# BV100011_ControlDO.net
KiCad netlist of a schematic drawn in Altium Designer
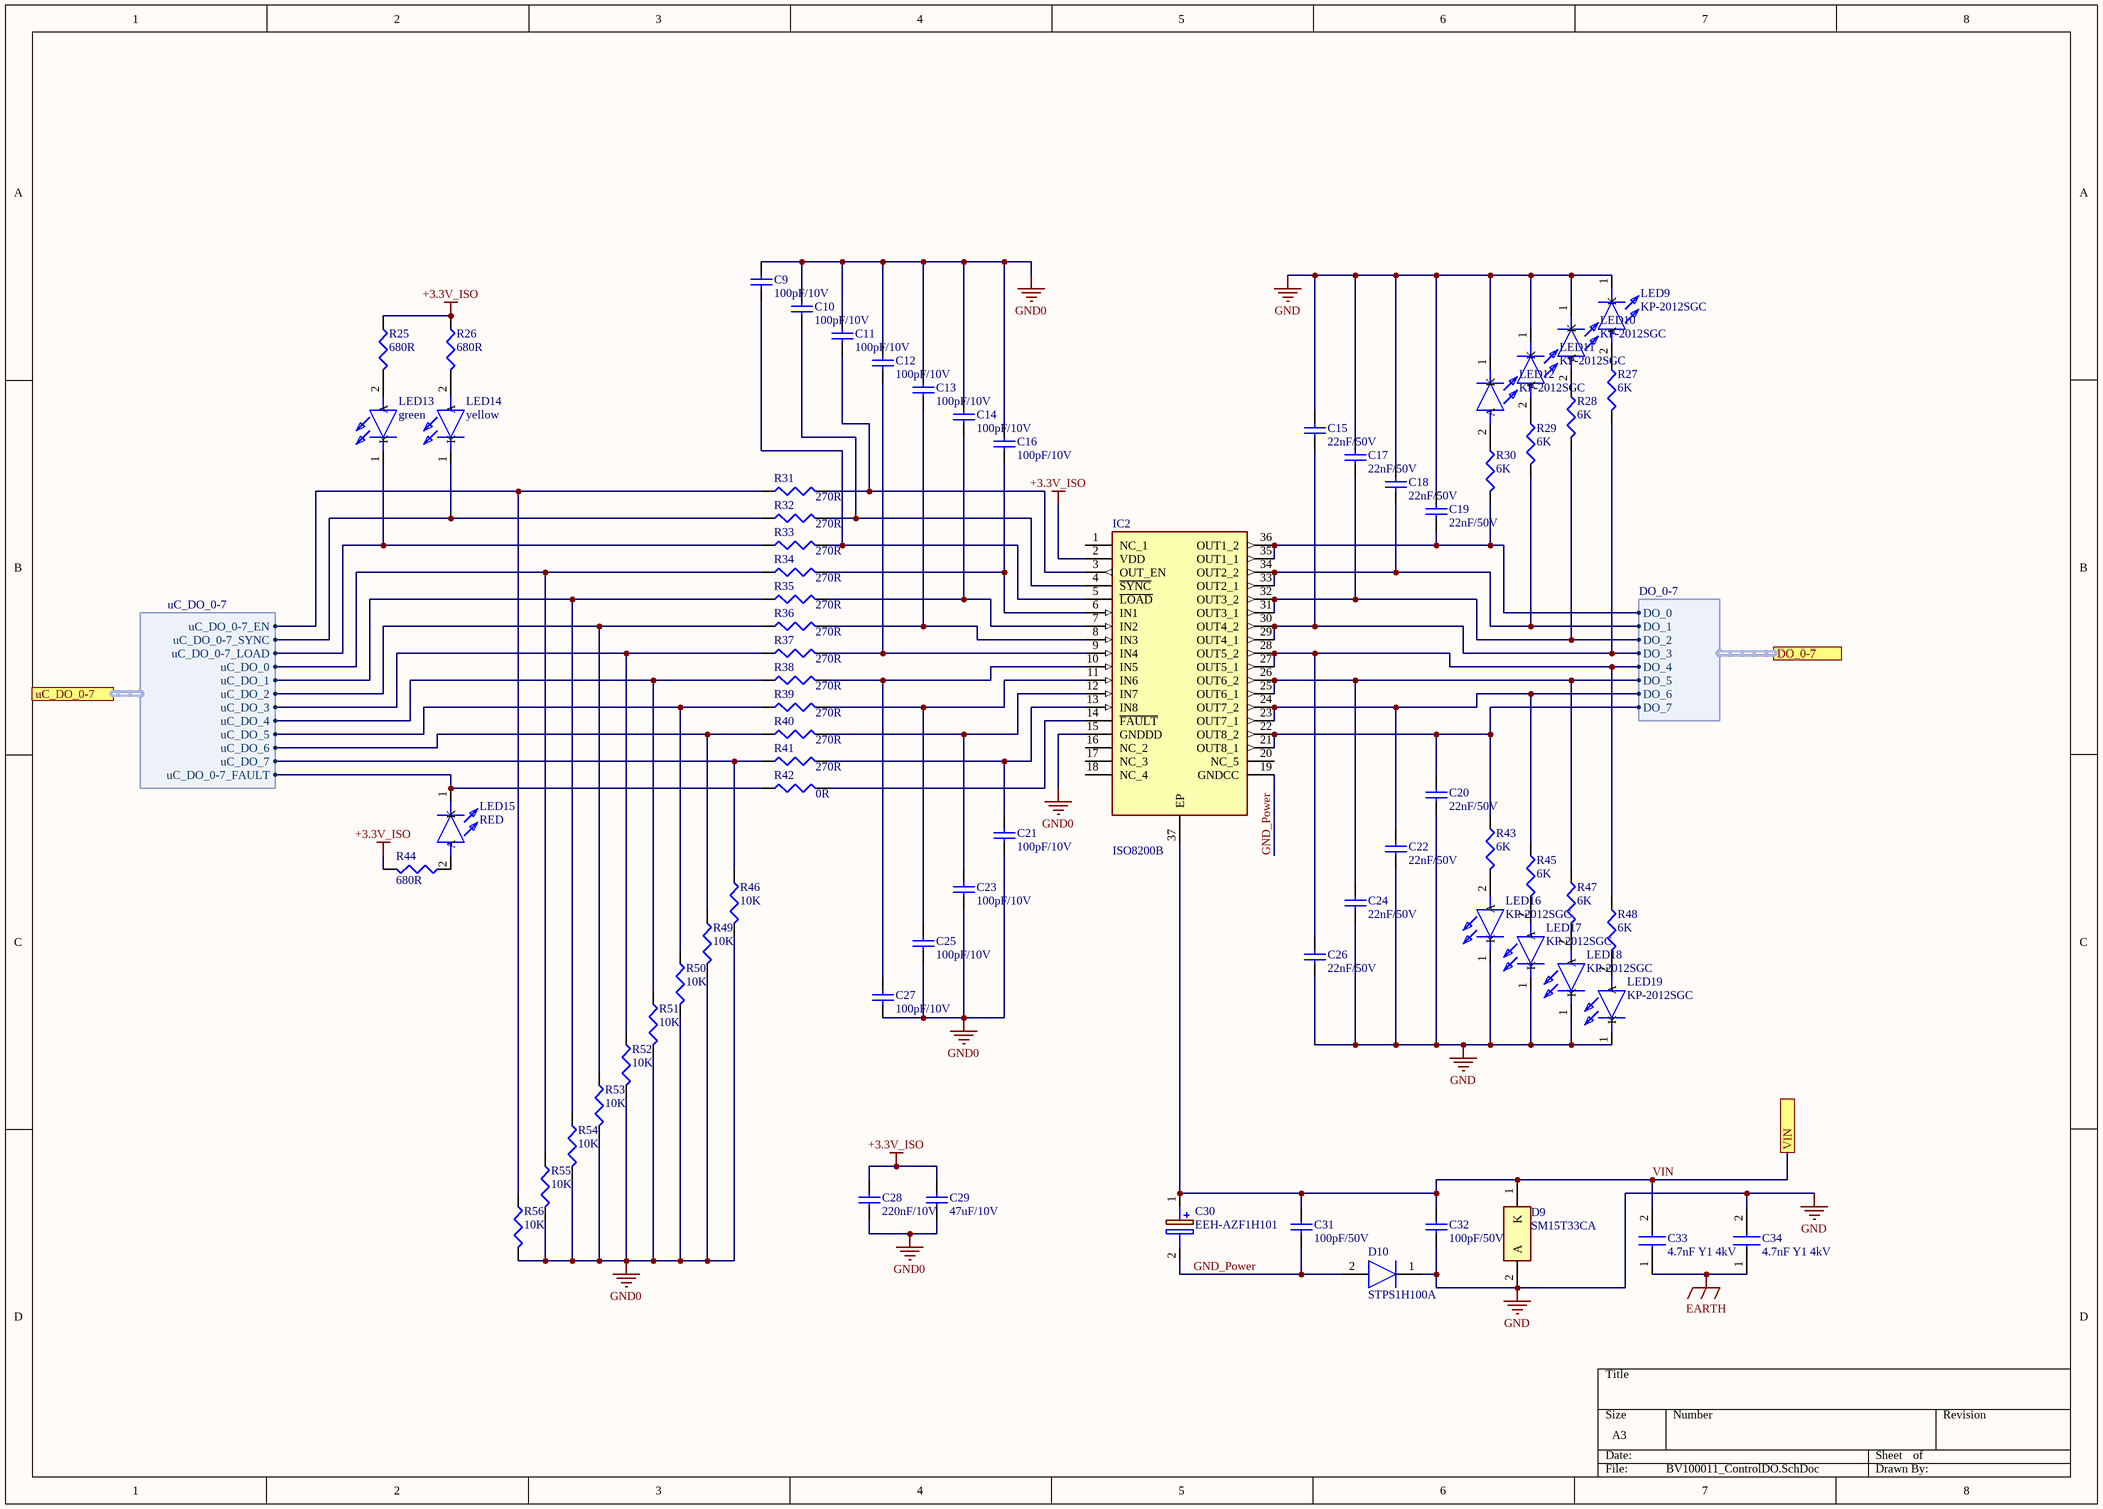
[diagram p0: BV100011_ControlDO.SchDoc]

(export (version "E")
  (design (tool "Eeschema 10.0.6"))
  (components
    (comp (ref "C9")
      (value "100pF/10V")
      (footprint "0402")
      (description "Capacitor (Semiconductor SIM Model)")
      (fields (field (name "PUBLISHER") "Altium Limited"))
      (libsource (lib "Miscellaneous Devices") (part "Cap Semi"))
    )
    (comp (ref "C10")
      (value "100pF/10V")
      (footprint "0402")
      (description "Capacitor (Semiconductor SIM Model)")
      (fields (field (name "PUBLISHER") "Altium Limited"))
      (libsource (lib "Miscellaneous Devices") (part "Cap Semi"))
    )
    (comp (ref "C11")
      (value "100pF/10V")
      (footprint "0402")
      (description "Capacitor (Semiconductor SIM Model)")
      (fields (field (name "PUBLISHER") "Altium Limited"))
      (libsource (lib "Miscellaneous Devices") (part "Cap Semi"))
    )
    (comp (ref "C12")
      (value "100pF/10V")
      (footprint "0402")
      (description "Capacitor (Semiconductor SIM Model)")
      (fields (field (name "PUBLISHER") "Altium Limited"))
      (libsource (lib "Miscellaneous Devices") (part "Cap Semi"))
    )
    (comp (ref "C13")
      (value "100pF/10V")
      (footprint "0402")
      (description "Capacitor (Semiconductor SIM Model)")
      (fields (field (name "PUBLISHER") "Altium Limited"))
      (libsource (lib "Miscellaneous Devices") (part "Cap Semi"))
    )
    (comp (ref "C14")
      (value "100pF/10V")
      (footprint "0402")
      (description "Capacitor (Semiconductor SIM Model)")
      (fields (field (name "PUBLISHER") "Altium Limited"))
      (libsource (lib "Miscellaneous Devices") (part "Cap Semi"))
    )
    (comp (ref "C15")
      (value "22nF/50V")
      (footprint "C1210")
      (description "Capacitor (Semiconductor SIM Model)")
      (fields (field (name "PUBLISHER") "Altium Limited"))
      (libsource (lib "Miscellaneous Devices") (part "Cap Semi"))
    )
    (comp (ref "C16")
      (value "100pF/10V")
      (footprint "0402")
      (description "Capacitor (Semiconductor SIM Model)")
      (fields (field (name "PUBLISHER") "Altium Limited"))
      (libsource (lib "Miscellaneous Devices") (part "Cap Semi"))
    )
    (comp (ref "C17")
      (value "22nF/50V")
      (footprint "C1210")
      (description "Capacitor (Semiconductor SIM Model)")
      (fields (field (name "PUBLISHER") "Altium Limited"))
      (libsource (lib "Miscellaneous Devices") (part "Cap Semi"))
    )
    (comp (ref "C18")
      (value "22nF/50V")
      (footprint "C1210")
      (description "Capacitor (Semiconductor SIM Model)")
      (fields (field (name "PUBLISHER") "Altium Limited"))
      (libsource (lib "Miscellaneous Devices") (part "Cap Semi"))
    )
    (comp (ref "C19")
      (value "22nF/50V")
      (footprint "C1210")
      (description "Capacitor (Semiconductor SIM Model)")
      (fields (field (name "PUBLISHER") "Altium Limited"))
      (libsource (lib "Miscellaneous Devices") (part "Cap Semi"))
    )
    (comp (ref "C20")
      (value "22nF/50V")
      (footprint "C1210")
      (description "Capacitor (Semiconductor SIM Model)")
      (fields (field (name "PUBLISHER") "Altium Limited"))
      (libsource (lib "Miscellaneous Devices") (part "Cap Semi"))
    )
    (comp (ref "C21")
      (value "100pF/10V")
      (footprint "0402")
      (description "Capacitor (Semiconductor SIM Model)")
      (fields (field (name "PUBLISHER") "Altium Limited"))
      (libsource (lib "Miscellaneous Devices") (part "Cap Semi"))
    )
    (comp (ref "C22")
      (value "22nF/50V")
      (footprint "C1210")
      (description "Capacitor (Semiconductor SIM Model)")
      (fields (field (name "PUBLISHER") "Altium Limited"))
      (libsource (lib "Miscellaneous Devices") (part "Cap Semi"))
    )
    (comp (ref "C23")
      (value "100pF/10V")
      (footprint "0402")
      (description "Capacitor (Semiconductor SIM Model)")
      (fields (field (name "PUBLISHER") "Altium Limited"))
      (libsource (lib "Miscellaneous Devices") (part "Cap Semi"))
    )
    (comp (ref "C24")
      (value "22nF/50V")
      (footprint "C1210")
      (description "Capacitor (Semiconductor SIM Model)")
      (fields (field (name "PUBLISHER") "Altium Limited"))
      (libsource (lib "Miscellaneous Devices") (part "Cap Semi"))
    )
    (comp (ref "C25")
      (value "100pF/10V")
      (footprint "0402")
      (description "Capacitor (Semiconductor SIM Model)")
      (fields (field (name "PUBLISHER") "Altium Limited"))
      (libsource (lib "Miscellaneous Devices") (part "Cap Semi"))
    )
    (comp (ref "C26")
      (value "22nF/50V")
      (footprint "C1210")
      (description "Capacitor (Semiconductor SIM Model)")
      (fields (field (name "PUBLISHER") "Altium Limited"))
      (libsource (lib "Miscellaneous Devices") (part "Cap Semi"))
    )
    (comp (ref "C27")
      (value "100pF/10V")
      (footprint "0402")
      (description "Capacitor (Semiconductor SIM Model)")
      (fields (field (name "PUBLISHER") "Altium Limited"))
      (libsource (lib "Miscellaneous Devices") (part "Cap Semi"))
    )
    (comp (ref "C28")
      (value "220nF/10V")
      (footprint "C1210")
      (description "Capacitor (Semiconductor SIM Model)")
      (fields (field (name "PUBLISHER") "Altium Limited"))
      (libsource (lib "Miscellaneous Devices") (part "Cap Semi"))
    )
    (comp (ref "C29")
      (value "47uF/10V")
      (footprint "C1210")
      (description "Capacitor (Semiconductor SIM Model)")
      (fields (field (name "PUBLISHER") "Altium Limited"))
      (libsource (lib "Miscellaneous Devices") (part "Cap Semi"))
    )
    (comp (ref "C30")
      (value "EEH-AZF1H101")
      (footprint "CAPPRD500W65D1000H1050")
      (description "Capacitor Polarised")
      (fields (field (name "MOUSER PART NUMBER") "667-EEH-AZF1H101"))
      (libsource (lib "Electrolytic Capacitors") (part "EEH-AZF1H101"))
    )
    (comp (ref "C31")
      (value "100pF/50V")
      (footprint "C1210")
      (description "Capacitor (Semiconductor SIM Model)")
      (fields (field (name "PUBLISHER") "Altium Limited"))
      (libsource (lib "Miscellaneous Devices") (part "Cap Semi"))
    )
    (comp (ref "C32")
      (value "100pF/50V")
      (footprint "C1210")
      (description "Capacitor (Semiconductor SIM Model)")
      (fields (field (name "PUBLISHER") "Altium Limited"))
      (libsource (lib "Miscellaneous Devices") (part "Cap Semi"))
    )
    (comp (ref "C33")
      (value "4.7nF Y1 4kV")
      (footprint "VY1472M63Y5UQ63V0")
      (description "Capacitor")
      (fields (field (name "MANUFACTURER_PART_NUMBER") "VY1472M63Y5UQ63V0"))
      (libsource (lib "VY1472M63Y5UQ6V0") (part "VY1472M63Y5UQ63V0"))
    )
    (comp (ref "C34")
      (value "4.7nF Y1 4kV")
      (footprint "VY1472M63Y5UQ63V0")
      (description "Capacitor")
      (fields (field (name "MANUFACTURER_PART_NUMBER") "VY1472M63Y5UQ63V0"))
      (libsource (lib "VY1472M63Y5UQ6V0") (part "VY1472M63Y5UQ63V0"))
    )
    (comp (ref "D9")
      (value "SM15T33CA")
      (footprint "DIONM8059X265N")
      (description "Diode")
      (fields (field (name "MOUSER PART NUMBER") "511-SM15T33CA") (field (name "RS PART NUMBER") "9196428"))
      (libsource (lib "SM15T33CA") (part "SM15T33CA"))
    )
    (comp (ref "D10")
      (value "STPS1H100A")
      (footprint "DIOM5126X265N")
      (description "Diode")
      (fields (field (name "MOUSER PART NUMBER") "511-STPS1H100A") (field (name "RS PART NUMBER") "0249892P"))
      (libsource (lib "STPS1H100A") (part "STPS1H100A"))
    )
    (comp (ref "IC2")
      (value "ISO8200B")
      (footprint "SOP65P1420X360-37N")
      (description "Integrated Circuit")
      (fields (field (name "MOUSER PART NUMBER") "511-ISO8200B"))
      (libsource (lib "ISO8200B") (part "ISO8200B"))
    )
    (comp (ref "LED9")
      (value "KP-2012SGC")
      (footprint "LEDC2012X110N")
      (description "LED")
      (fields (field (name "RS PART NUMBER") "4663807"))
      (libsource (lib "POWER_LED") (part "KP-2012SGC"))
    )
    (comp (ref "LED10")
      (value "KP-2012SGC")
      (footprint "LEDC2012X110N")
      (description "LED")
      (fields (field (name "RS PART NUMBER") "4663807"))
      (libsource (lib "POWER_LED") (part "KP-2012SGC"))
    )
    (comp (ref "LED11")
      (value "KP-2012SGC")
      (footprint "LEDC2012X110N")
      (description "LED")
      (fields (field (name "RS PART NUMBER") "4663807"))
      (libsource (lib "POWER_LED") (part "KP-2012SGC"))
    )
    (comp (ref "LED12")
      (value "KP-2012SGC")
      (footprint "LEDC2012X110N")
      (description "LED")
      (fields (field (name "RS PART NUMBER") "4663807"))
      (libsource (lib "POWER_LED") (part "KP-2012SGC"))
    )
    (comp (ref "LED13")
      (value "green")
      (footprint "LEDC2012X110N")
      (description "LED")
      (fields
        (field (name "MANUFACTURER_PART_NUMBER") "KP-2012SGC")
        (field (name "RS PART NUMBER") "4663807")
      )
      (libsource (lib "POWER_LED") (part "KP-2012SGC"))
    )
    (comp (ref "LED14")
      (value "yellow")
      (footprint "LEDC2012X110N")
      (description "LED")
      (fields
        (field (name "MANUFACTURER_PART_NUMBER") "KP-2012SGC")
        (field (name "RS PART NUMBER") "4663807")
      )
      (libsource (lib "POWER_LED") (part "KP-2012SGC"))
    )
    (comp (ref "LED15")
      (value "RED")
      (footprint "LEDC2012X110N")
      (description "LED")
      (fields
        (field (name "MANUFACTURER_PART_NUMBER") "KP-2012SGC")
        (field (name "RS PART NUMBER") "4663807")
      )
      (libsource (lib "POWER_LED") (part "KP-2012SGC"))
    )
    (comp (ref "LED16")
      (value "KP-2012SGC")
      (footprint "LEDC2012X110N")
      (description "LED")
      (fields (field (name "RS PART NUMBER") "4663807"))
      (libsource (lib "POWER_LED") (part "KP-2012SGC"))
    )
    (comp (ref "LED17")
      (value "KP-2012SGC")
      (footprint "LEDC2012X110N")
      (description "LED")
      (fields (field (name "RS PART NUMBER") "4663807"))
      (libsource (lib "POWER_LED") (part "KP-2012SGC"))
    )
    (comp (ref "LED18")
      (value "KP-2012SGC")
      (footprint "LEDC2012X110N")
      (description "LED")
      (fields (field (name "RS PART NUMBER") "4663807"))
      (libsource (lib "POWER_LED") (part "KP-2012SGC"))
    )
    (comp (ref "LED19")
      (value "KP-2012SGC")
      (footprint "LEDC2012X110N")
      (description "LED")
      (fields (field (name "RS PART NUMBER") "4663807"))
      (libsource (lib "POWER_LED") (part "KP-2012SGC"))
    )
    (comp (ref "R25")
      (value "680R")
      (footprint "0402")
      (description "Resistor")
      (fields (field (name "PUBLISHER") "Altium Limited"))
      (libsource (lib "Miscellaneous Devices") (part "Res3"))
    )
    (comp (ref "R26")
      (value "680R")
      (footprint "0402")
      (description "Resistor")
      (fields (field (name "PUBLISHER") "Altium Limited"))
      (libsource (lib "Miscellaneous Devices") (part "Res3"))
    )
    (comp (ref "R27")
      (value "6K")
      (footprint "0805R")
      (description "Resistor")
      (fields (field (name "PUBLISHER") "Altium Limited"))
      (libsource (lib "Miscellaneous Devices") (part "Res3"))
    )
    (comp (ref "R28")
      (value "6K")
      (footprint "0805R")
      (description "Resistor")
      (fields (field (name "PUBLISHER") "Altium Limited"))
      (libsource (lib "Miscellaneous Devices") (part "Res3"))
    )
    (comp (ref "R29")
      (value "6K")
      (footprint "0805R")
      (description "Resistor")
      (fields (field (name "PUBLISHER") "Altium Limited"))
      (libsource (lib "Miscellaneous Devices") (part "Res3"))
    )
    (comp (ref "R30")
      (value "6K")
      (footprint "0805R")
      (description "Resistor")
      (fields (field (name "PUBLISHER") "Altium Limited"))
      (libsource (lib "Miscellaneous Devices") (part "Res3"))
    )
    (comp (ref "R31")
      (value "270R")
      (footprint "0402")
      (description "Resistor")
      (fields (field (name "PUBLISHER") "Altium Limited"))
      (libsource (lib "Miscellaneous Devices") (part "Res3"))
    )
    (comp (ref "R32")
      (value "270R")
      (footprint "0402")
      (description "Resistor")
      (fields (field (name "PUBLISHER") "Altium Limited"))
      (libsource (lib "Miscellaneous Devices") (part "Res3"))
    )
    (comp (ref "R33")
      (value "270R")
      (footprint "0402")
      (description "Resistor")
      (fields (field (name "PUBLISHER") "Altium Limited"))
      (libsource (lib "Miscellaneous Devices") (part "Res3"))
    )
    (comp (ref "R34")
      (value "270R")
      (footprint "0402")
      (description "Resistor")
      (fields (field (name "PUBLISHER") "Altium Limited"))
      (libsource (lib "Miscellaneous Devices") (part "Res3"))
    )
    (comp (ref "R35")
      (value "270R")
      (footprint "0402")
      (description "Resistor")
      (fields (field (name "PUBLISHER") "Altium Limited"))
      (libsource (lib "Miscellaneous Devices") (part "Res3"))
    )
    (comp (ref "R36")
      (value "270R")
      (footprint "0402")
      (description "Resistor")
      (fields (field (name "PUBLISHER") "Altium Limited"))
      (libsource (lib "Miscellaneous Devices") (part "Res3"))
    )
    (comp (ref "R37")
      (value "270R")
      (footprint "0402")
      (description "Resistor")
      (fields (field (name "PUBLISHER") "Altium Limited"))
      (libsource (lib "Miscellaneous Devices") (part "Res3"))
    )
    (comp (ref "R38")
      (value "270R")
      (footprint "0402")
      (description "Resistor")
      (fields (field (name "PUBLISHER") "Altium Limited"))
      (libsource (lib "Miscellaneous Devices") (part "Res3"))
    )
    (comp (ref "R39")
      (value "270R")
      (footprint "0402")
      (description "Resistor")
      (fields (field (name "PUBLISHER") "Altium Limited"))
      (libsource (lib "Miscellaneous Devices") (part "Res3"))
    )
    (comp (ref "R40")
      (value "270R")
      (footprint "0402")
      (description "Resistor")
      (fields (field (name "PUBLISHER") "Altium Limited"))
      (libsource (lib "Miscellaneous Devices") (part "Res3"))
    )
    (comp (ref "R41")
      (value "270R")
      (footprint "0402")
      (description "Resistor")
      (fields (field (name "PUBLISHER") "Altium Limited"))
      (libsource (lib "Miscellaneous Devices") (part "Res3"))
    )
    (comp (ref "R42")
      (value "0R")
      (footprint "0402")
      (description "Resistor")
      (fields (field (name "PUBLISHER") "Altium Limited"))
      (libsource (lib "Miscellaneous Devices") (part "Res3"))
    )
    (comp (ref "R43")
      (value "6K")
      (footprint "0805R")
      (description "Resistor")
      (fields (field (name "PUBLISHER") "Altium Limited"))
      (libsource (lib "Miscellaneous Devices") (part "Res3"))
    )
    (comp (ref "R44")
      (value "680R")
      (footprint "0402")
      (description "Resistor")
      (fields (field (name "PUBLISHER") "Altium Limited"))
      (libsource (lib "Miscellaneous Devices") (part "Res3"))
    )
    (comp (ref "R45")
      (value "6K")
      (footprint "0805R")
      (description "Resistor")
      (fields (field (name "PUBLISHER") "Altium Limited"))
      (libsource (lib "Miscellaneous Devices") (part "Res3"))
    )
    (comp (ref "R46")
      (value "10K")
      (footprint "0402")
      (description "Resistor")
      (fields (field (name "PUBLISHER") "Altium Limited"))
      (libsource (lib "Miscellaneous Devices") (part "Res3"))
    )
    (comp (ref "R47")
      (value "6K")
      (footprint "0805R")
      (description "Resistor")
      (fields (field (name "PUBLISHER") "Altium Limited"))
      (libsource (lib "Miscellaneous Devices") (part "Res3"))
    )
    (comp (ref "R48")
      (value "6K")
      (footprint "0805R")
      (description "Resistor")
      (fields (field (name "PUBLISHER") "Altium Limited"))
      (libsource (lib "Miscellaneous Devices") (part "Res3"))
    )
    (comp (ref "R49")
      (value "10K")
      (footprint "0402")
      (description "Resistor")
      (fields (field (name "PUBLISHER") "Altium Limited"))
      (libsource (lib "Miscellaneous Devices") (part "Res3"))
    )
    (comp (ref "R50")
      (value "10K")
      (footprint "0402")
      (description "Resistor")
      (fields (field (name "PUBLISHER") "Altium Limited"))
      (libsource (lib "Miscellaneous Devices") (part "Res3"))
    )
    (comp (ref "R51")
      (value "10K")
      (footprint "0402")
      (description "Resistor")
      (fields (field (name "PUBLISHER") "Altium Limited"))
      (libsource (lib "Miscellaneous Devices") (part "Res3"))
    )
    (comp (ref "R52")
      (value "10K")
      (footprint "0402")
      (description "Resistor")
      (fields (field (name "PUBLISHER") "Altium Limited"))
      (libsource (lib "Miscellaneous Devices") (part "Res3"))
    )
    (comp (ref "R53")
      (value "10K")
      (footprint "0402")
      (description "Resistor")
      (fields (field (name "PUBLISHER") "Altium Limited"))
      (libsource (lib "Miscellaneous Devices") (part "Res3"))
    )
    (comp (ref "R54")
      (value "10K")
      (footprint "0402")
      (description "Resistor")
      (fields (field (name "PUBLISHER") "Altium Limited"))
      (libsource (lib "Miscellaneous Devices") (part "Res3"))
    )
    (comp (ref "R55")
      (value "10K")
      (footprint "0402")
      (description "Resistor")
      (fields (field (name "PUBLISHER") "Altium Limited"))
      (libsource (lib "Miscellaneous Devices") (part "Res3"))
    )
    (comp (ref "R56")
      (value "10K")
      (footprint "0402")
      (description "Resistor")
      (fields (field (name "PUBLISHER") "Altium Limited"))
      (libsource (lib "Miscellaneous Devices") (part "Res3"))
    )
  )
  (nets
    (net (code "3") (name "+3.3V_ISO") (class "Default")
      (node (ref "C28") (pin "2") (pinfunction "2_2") (pintype "passive"))
      (node (ref "C29") (pin "2") (pinfunction "2_2") (pintype "passive"))
      (node (ref "IC2") (pin "2") (pinfunction "VDD_2") (pintype "power_in"))
      (node (ref "R25") (pin "1") (pinfunction "1_1") (pintype "passive"))
      (node (ref "R26") (pin "1") (pinfunction "1_1") (pintype "passive"))
      (node (ref "R44") (pin "2") (pinfunction "2_2") (pintype "passive"))
    )
    (net (code "4") (name "/GND_Power") (class "Default")
      (node (ref "C30") (pin "2") (pinfunction "-_2") (pintype "passive"))
      (node (ref "C31") (pin "1") (pinfunction "1_1") (pintype "passive"))
      (node (ref "D10") (pin "2") (pinfunction "A_2") (pintype "passive"))
      (node (ref "IC2") (pin "19") (pinfunction "GNDCC_19") (pintype "power_in"))
    )
    (net (code "5") (name "/VIN") (class "Default")
      (node (ref "C30") (pin "1") (pinfunction "+_1") (pintype "passive"))
      (node (ref "C31") (pin "2") (pinfunction "2_2") (pintype "passive"))
      (node (ref "C32") (pin "2") (pinfunction "2_2") (pintype "passive"))
      (node (ref "C33") (pin "2") (pinfunction "2_2") (pintype "passive"))
      (node (ref "D9") (pin "1") (pinfunction "K_1") (pintype "passive"))
      (node (ref "IC2") (pin "37") (pinfunction "EP_37") (pintype "power_in"))
    )
    (net (code "8") (name "EARTH") (class "Default")
      (node (ref "C33") (pin "1") (pinfunction "1_1") (pintype "passive"))
      (node (ref "C34") (pin "1") (pinfunction "1_1") (pintype "passive"))
    )
    (net (code "9") (name "GND") (class "Default")
      (node (ref "C15") (pin "1") (pinfunction "1_1") (pintype "passive"))
      (node (ref "C17") (pin "1") (pinfunction "1_1") (pintype "passive"))
      (node (ref "C18") (pin "1") (pinfunction "1_1") (pintype "passive"))
      (node (ref "C19") (pin "1") (pinfunction "1_1") (pintype "passive"))
      (node (ref "C20") (pin "2") (pinfunction "2_2") (pintype "passive"))
      (node (ref "C22") (pin "2") (pinfunction "2_2") (pintype "passive"))
      (node (ref "C24") (pin "2") (pinfunction "2_2") (pintype "passive"))
      (node (ref "C26") (pin "2") (pinfunction "2_2") (pintype "passive"))
      (node (ref "C32") (pin "1") (pinfunction "1_1") (pintype "passive"))
      (node (ref "C34") (pin "2") (pinfunction "2_2") (pintype "passive"))
      (node (ref "D10") (pin "1") (pinfunction "K_1") (pintype "passive"))
      (node (ref "D9") (pin "2") (pinfunction "A_2") (pintype "passive"))
      (node (ref "LED10") (pin "1") (pinfunction "K_1") (pintype "passive"))
      (node (ref "LED11") (pin "1") (pinfunction "K_1") (pintype "passive"))
      (node (ref "LED12") (pin "1") (pinfunction "K_1") (pintype "passive"))
      (node (ref "LED16") (pin "1") (pinfunction "K_1") (pintype "passive"))
      (node (ref "LED17") (pin "1") (pinfunction "K_1") (pintype "passive"))
      (node (ref "LED18") (pin "1") (pinfunction "K_1") (pintype "passive"))
      (node (ref "LED19") (pin "1") (pinfunction "K_1") (pintype "passive"))
      (node (ref "LED9") (pin "1") (pinfunction "K_1") (pintype "passive"))
    )
    (net (code "10") (name "GND0") (class "Default")
      (node (ref "C10") (pin "1") (pinfunction "1_1") (pintype "passive"))
      (node (ref "C11") (pin "1") (pinfunction "1_1") (pintype "passive"))
      (node (ref "C12") (pin "1") (pinfunction "1_1") (pintype "passive"))
      (node (ref "C13") (pin "1") (pinfunction "1_1") (pintype "passive"))
      (node (ref "C14") (pin "1") (pinfunction "1_1") (pintype "passive"))
      (node (ref "C16") (pin "1") (pinfunction "1_1") (pintype "passive"))
      (node (ref "C21") (pin "2") (pinfunction "2_2") (pintype "passive"))
      (node (ref "C23") (pin "2") (pinfunction "2_2") (pintype "passive"))
      (node (ref "C25") (pin "2") (pinfunction "2_2") (pintype "passive"))
      (node (ref "C27") (pin "2") (pinfunction "2_2") (pintype "passive"))
      (node (ref "C28") (pin "1") (pinfunction "1_1") (pintype "passive"))
      (node (ref "C29") (pin "1") (pinfunction "1_1") (pintype "passive"))
      (node (ref "C9") (pin "1") (pinfunction "1_1") (pintype "passive"))
      (node (ref "IC2") (pin "15") (pinfunction "GNDDD_15") (pintype "power_in"))
      (node (ref "R46") (pin "2") (pinfunction "2_2") (pintype "passive"))
      (node (ref "R49") (pin "2") (pinfunction "2_2") (pintype "passive"))
      (node (ref "R50") (pin "2") (pinfunction "2_2") (pintype "passive"))
      (node (ref "R51") (pin "2") (pinfunction "2_2") (pintype "passive"))
      (node (ref "R52") (pin "2") (pinfunction "2_2") (pintype "passive"))
      (node (ref "R53") (pin "2") (pinfunction "2_2") (pintype "passive"))
      (node (ref "R54") (pin "2") (pinfunction "2_2") (pintype "passive"))
      (node (ref "R55") (pin "2") (pinfunction "2_2") (pintype "passive"))
      (node (ref "R56") (pin "2") (pinfunction "2_2") (pintype "passive"))
    )
    (net (code "11") (name "Net-(IC2-IN1)") (class "Default")
      (node (ref "C16") (pin "2") (pinfunction "2_2") (pintype "passive"))
      (node (ref "IC2") (pin "6") (pinfunction "IN1_6") (pintype "input"))
      (node (ref "R34") (pin "2") (pinfunction "2_2") (pintype "passive"))
    )
    (net (code "12") (name "Net-(IC2-IN2)") (class "Default")
      (node (ref "C14") (pin "2") (pinfunction "2_2") (pintype "passive"))
      (node (ref "IC2") (pin "7") (pinfunction "IN2_7") (pintype "input"))
      (node (ref "R35") (pin "2") (pinfunction "2_2") (pintype "passive"))
    )
    (net (code "13") (name "Net-(IC2-IN3)") (class "Default")
      (node (ref "C13") (pin "2") (pinfunction "2_2") (pintype "passive"))
      (node (ref "IC2") (pin "8") (pinfunction "IN3_8") (pintype "input"))
      (node (ref "R36") (pin "2") (pinfunction "2_2") (pintype "passive"))
    )
    (net (code "14") (name "Net-(IC2-IN4)") (class "Default")
      (node (ref "C12") (pin "2") (pinfunction "2_2") (pintype "passive"))
      (node (ref "IC2") (pin "9") (pinfunction "IN4_9") (pintype "input"))
      (node (ref "R37") (pin "2") (pinfunction "2_2") (pintype "passive"))
    )
    (net (code "15") (name "Net-(IC2-IN5)") (class "Default")
      (node (ref "C27") (pin "1") (pinfunction "1_1") (pintype "passive"))
      (node (ref "IC2") (pin "10") (pinfunction "IN5_10") (pintype "input"))
      (node (ref "R38") (pin "2") (pinfunction "2_2") (pintype "passive"))
    )
    (net (code "16") (name "Net-(IC2-IN6)") (class "Default")
      (node (ref "C25") (pin "1") (pinfunction "1_1") (pintype "passive"))
      (node (ref "IC2") (pin "11") (pinfunction "IN6_11") (pintype "input"))
      (node (ref "R39") (pin "2") (pinfunction "2_2") (pintype "passive"))
    )
    (net (code "17") (name "Net-(IC2-IN7)") (class "Default")
      (node (ref "C23") (pin "1") (pinfunction "1_1") (pintype "passive"))
      (node (ref "IC2") (pin "12") (pinfunction "IN7_12") (pintype "input"))
      (node (ref "R40") (pin "2") (pinfunction "2_2") (pintype "passive"))
    )
    (net (code "18") (name "Net-(IC2-IN8)") (class "Default")
      (node (ref "C21") (pin "1") (pinfunction "1_1") (pintype "passive"))
      (node (ref "IC2") (pin "13") (pinfunction "IN8_13") (pintype "input"))
      (node (ref "R41") (pin "2") (pinfunction "2_2") (pintype "passive"))
    )
    (net (code "19") (name "Net-(IC2-OUT1_1)") (class "Default")
      (node (ref "C19") (pin "2") (pinfunction "2_2") (pintype "passive"))
      (node (ref "IC2") (pin "35") (pinfunction "OUT1_1_35") (pintype "output"))
      (node (ref "IC2") (pin "36") (pinfunction "OUT1_2_36") (pintype "output"))
      (node (ref "R30") (pin "2") (pinfunction "2_2") (pintype "passive"))
    )
    (net (code "20") (name "Net-(IC2-OUT2_1)") (class "Default")
      (node (ref "C18") (pin "2") (pinfunction "2_2") (pintype "passive"))
      (node (ref "IC2") (pin "33") (pinfunction "OUT2_1_33") (pintype "output"))
      (node (ref "IC2") (pin "34") (pinfunction "OUT2_2_34") (pintype "output"))
      (node (ref "R29") (pin "2") (pinfunction "2_2") (pintype "passive"))
    )
    (net (code "21") (name "Net-(IC2-OUT3_1)") (class "Default")
      (node (ref "C17") (pin "2") (pinfunction "2_2") (pintype "passive"))
      (node (ref "IC2") (pin "31") (pinfunction "OUT3_1_31") (pintype "output"))
      (node (ref "IC2") (pin "32") (pinfunction "OUT3_2_32") (pintype "output"))
      (node (ref "R28") (pin "2") (pinfunction "2_2") (pintype "passive"))
    )
    (net (code "22") (name "Net-(IC2-OUT4_1)") (class "Default")
      (node (ref "C15") (pin "2") (pinfunction "2_2") (pintype "passive"))
      (node (ref "IC2") (pin "29") (pinfunction "OUT4_1_29") (pintype "output"))
      (node (ref "IC2") (pin "30") (pinfunction "OUT4_2_30") (pintype "output"))
      (node (ref "R27") (pin "2") (pinfunction "2_2") (pintype "passive"))
    )
    (net (code "23") (name "Net-(IC2-OUT5_1)") (class "Default")
      (node (ref "C26") (pin "1") (pinfunction "1_1") (pintype "passive"))
      (node (ref "IC2") (pin "27") (pinfunction "OUT5_1_27") (pintype "output"))
      (node (ref "IC2") (pin "28") (pinfunction "OUT5_2_28") (pintype "output"))
      (node (ref "R48") (pin "1") (pinfunction "1_1") (pintype "passive"))
    )
    (net (code "24") (name "Net-(IC2-OUT6_1)") (class "Default")
      (node (ref "C24") (pin "1") (pinfunction "1_1") (pintype "passive"))
      (node (ref "IC2") (pin "25") (pinfunction "OUT6_1_25") (pintype "output"))
      (node (ref "IC2") (pin "26") (pinfunction "OUT6_2_26") (pintype "output"))
      (node (ref "R47") (pin "1") (pinfunction "1_1") (pintype "passive"))
    )
    (net (code "25") (name "Net-(IC2-OUT7_1)") (class "Default")
      (node (ref "C22") (pin "1") (pinfunction "1_1") (pintype "passive"))
      (node (ref "IC2") (pin "23") (pinfunction "OUT7_1_23") (pintype "output"))
      (node (ref "IC2") (pin "24") (pinfunction "OUT7_2_24") (pintype "output"))
      (node (ref "R45") (pin "1") (pinfunction "1_1") (pintype "passive"))
    )
    (net (code "26") (name "Net-(IC2-OUT8_1)") (class "Default")
      (node (ref "C20") (pin "1") (pinfunction "1_1") (pintype "passive"))
      (node (ref "IC2") (pin "21") (pinfunction "OUT8_1_21") (pintype "output"))
      (node (ref "IC2") (pin "22") (pinfunction "OUT8_2_22") (pintype "output"))
      (node (ref "R43") (pin "1") (pinfunction "1_1") (pintype "passive"))
    )
    (net (code "27") (name "Net-(IC2-OUT_EN)") (class "Default")
      (node (ref "C11") (pin "2") (pinfunction "2_2") (pintype "passive"))
      (node (ref "IC2") (pin "3") (pinfunction "OUT_EN_3") (pintype "output"))
      (node (ref "R31") (pin "2") (pinfunction "2_2") (pintype "passive"))
    )
    (net (code "28") (name "Net-(IC2-~{FAULT})") (class "Default")
      (node (ref "IC2") (pin "14") (pinfunction "~{FAULT}_14") (pintype "passive"))
      (node (ref "R42") (pin "2") (pinfunction "2_2") (pintype "passive"))
    )
    (net (code "29") (name "Net-(IC2-~{LOAD})") (class "Default")
      (node (ref "C9") (pin "2") (pinfunction "2_2") (pintype "passive"))
      (node (ref "IC2") (pin "5") (pinfunction "~{LOAD}_5") (pintype "passive"))
      (node (ref "R33") (pin "2") (pinfunction "2_2") (pintype "passive"))
    )
    (net (code "30") (name "Net-(IC2-~{SYNC})") (class "Default")
      (node (ref "C10") (pin "2") (pinfunction "2_2") (pintype "passive"))
      (node (ref "IC2") (pin "4") (pinfunction "~{SYNC}_4") (pintype "passive"))
      (node (ref "R32") (pin "2") (pinfunction "2_2") (pintype "passive"))
    )
    (net (code "31") (name "Net-(LED9-A)") (class "Default")
      (node (ref "LED9") (pin "2") (pinfunction "A_2") (pintype "passive"))
      (node (ref "R27") (pin "1") (pinfunction "1_1") (pintype "passive"))
    )
    (net (code "32") (name "Net-(LED10-A)") (class "Default")
      (node (ref "LED10") (pin "2") (pinfunction "A_2") (pintype "passive"))
      (node (ref "R28") (pin "1") (pinfunction "1_1") (pintype "passive"))
    )
    (net (code "33") (name "Net-(LED11-A)") (class "Default")
      (node (ref "LED11") (pin "2") (pinfunction "A_2") (pintype "passive"))
      (node (ref "R29") (pin "1") (pinfunction "1_1") (pintype "passive"))
    )
    (net (code "34") (name "Net-(LED12-A)") (class "Default")
      (node (ref "LED12") (pin "2") (pinfunction "A_2") (pintype "passive"))
      (node (ref "R30") (pin "1") (pinfunction "1_1") (pintype "passive"))
    )
    (net (code "35") (name "Net-(LED13-A)") (class "Default")
      (node (ref "LED13") (pin "2") (pinfunction "A_2") (pintype "passive"))
      (node (ref "R25") (pin "2") (pinfunction "2_2") (pintype "passive"))
    )
    (net (code "36") (name "Net-(LED13-K)") (class "Default")
      (node (ref "LED13") (pin "1") (pinfunction "K_1") (pintype "passive"))
      (node (ref "R33") (pin "1") (pinfunction "1_1") (pintype "passive"))
    )
    (net (code "37") (name "Net-(LED14-A)") (class "Default")
      (node (ref "LED14") (pin "2") (pinfunction "A_2") (pintype "passive"))
      (node (ref "R26") (pin "2") (pinfunction "2_2") (pintype "passive"))
    )
    (net (code "38") (name "Net-(LED14-K)") (class "Default")
      (node (ref "LED14") (pin "1") (pinfunction "K_1") (pintype "passive"))
      (node (ref "R32") (pin "1") (pinfunction "1_1") (pintype "passive"))
    )
    (net (code "39") (name "Net-(LED15-A)") (class "Default")
      (node (ref "LED15") (pin "2") (pinfunction "A_2") (pintype "passive"))
      (node (ref "R44") (pin "1") (pinfunction "1_1") (pintype "passive"))
    )
    (net (code "40") (name "Net-(LED15-K)") (class "Default")
      (node (ref "LED15") (pin "1") (pinfunction "K_1") (pintype "passive"))
      (node (ref "R42") (pin "1") (pinfunction "1_1") (pintype "passive"))
    )
    (net (code "41") (name "Net-(LED16-A)") (class "Default")
      (node (ref "LED16") (pin "2") (pinfunction "A_2") (pintype "passive"))
      (node (ref "R43") (pin "2") (pinfunction "2_2") (pintype "passive"))
    )
    (net (code "42") (name "Net-(LED17-A)") (class "Default")
      (node (ref "LED17") (pin "2") (pinfunction "A_2") (pintype "passive"))
      (node (ref "R45") (pin "2") (pinfunction "2_2") (pintype "passive"))
    )
    (net (code "43") (name "Net-(LED18-A)") (class "Default")
      (node (ref "LED18") (pin "2") (pinfunction "A_2") (pintype "passive"))
      (node (ref "R47") (pin "2") (pinfunction "2_2") (pintype "passive"))
    )
    (net (code "44") (name "Net-(LED19-A)") (class "Default")
      (node (ref "LED19") (pin "2") (pinfunction "A_2") (pintype "passive"))
      (node (ref "R48") (pin "2") (pinfunction "2_2") (pintype "passive"))
    )
    (net (code "45") (name "Net-(R31-Pad1)") (class "Default")
      (node (ref "R31") (pin "1") (pinfunction "1_1") (pintype "passive"))
      (node (ref "R56") (pin "1") (pinfunction "1_1") (pintype "passive"))
    )
    (net (code "46") (name "Net-(R34-Pad1)") (class "Default")
      (node (ref "R34") (pin "1") (pinfunction "1_1") (pintype "passive"))
      (node (ref "R55") (pin "1") (pinfunction "1_1") (pintype "passive"))
    )
    (net (code "47") (name "Net-(R35-Pad1)") (class "Default")
      (node (ref "R35") (pin "1") (pinfunction "1_1") (pintype "passive"))
      (node (ref "R54") (pin "1") (pinfunction "1_1") (pintype "passive"))
    )
    (net (code "48") (name "Net-(R36-Pad1)") (class "Default")
      (node (ref "R36") (pin "1") (pinfunction "1_1") (pintype "passive"))
      (node (ref "R53") (pin "1") (pinfunction "1_1") (pintype "passive"))
    )
    (net (code "49") (name "Net-(R37-Pad1)") (class "Default")
      (node (ref "R37") (pin "1") (pinfunction "1_1") (pintype "passive"))
      (node (ref "R52") (pin "1") (pinfunction "1_1") (pintype "passive"))
    )
    (net (code "50") (name "Net-(R38-Pad1)") (class "Default")
      (node (ref "R38") (pin "1") (pinfunction "1_1") (pintype "passive"))
      (node (ref "R51") (pin "1") (pinfunction "1_1") (pintype "passive"))
    )
    (net (code "51") (name "Net-(R39-Pad1)") (class "Default")
      (node (ref "R39") (pin "1") (pinfunction "1_1") (pintype "passive"))
      (node (ref "R50") (pin "1") (pinfunction "1_1") (pintype "passive"))
    )
    (net (code "52") (name "Net-(R40-Pad1)") (class "Default")
      (node (ref "R40") (pin "1") (pinfunction "1_1") (pintype "passive"))
      (node (ref "R49") (pin "1") (pinfunction "1_1") (pintype "passive"))
    )
    (net (code "53") (name "Net-(R41-Pad1)") (class "Default")
      (node (ref "R41") (pin "1") (pinfunction "1_1") (pintype "passive"))
      (node (ref "R46") (pin "1") (pinfunction "1_1") (pintype "passive"))
    )
    (net (code "54") (name "unconnected-(IC2-NC_1-Pad1)") (class "Default")
      (node (ref "IC2") (pin "1") (pinfunction "NC_1_1") (pintype "passive"))
    )
    (net (code "55") (name "unconnected-(IC2-NC_2-Pad16)") (class "Default")
      (node (ref "IC2") (pin "16") (pinfunction "NC_2_16") (pintype "passive"))
    )
    (net (code "56") (name "unconnected-(IC2-NC_3-Pad17)") (class "Default")
      (node (ref "IC2") (pin "17") (pinfunction "NC_3_17") (pintype "passive"))
    )
    (net (code "57") (name "unconnected-(IC2-NC_4-Pad18)") (class "Default")
      (node (ref "IC2") (pin "18") (pinfunction "NC_4_18") (pintype "passive"))
    )
    (net (code "58") (name "unconnected-(IC2-NC_5-Pad20)") (class "Default")
      (node (ref "IC2") (pin "20") (pinfunction "NC_5_20") (pintype "passive"))
    )
  )
)
